# board_1_2v.net
KiCad netlist of a schematic drawn in EAGLE
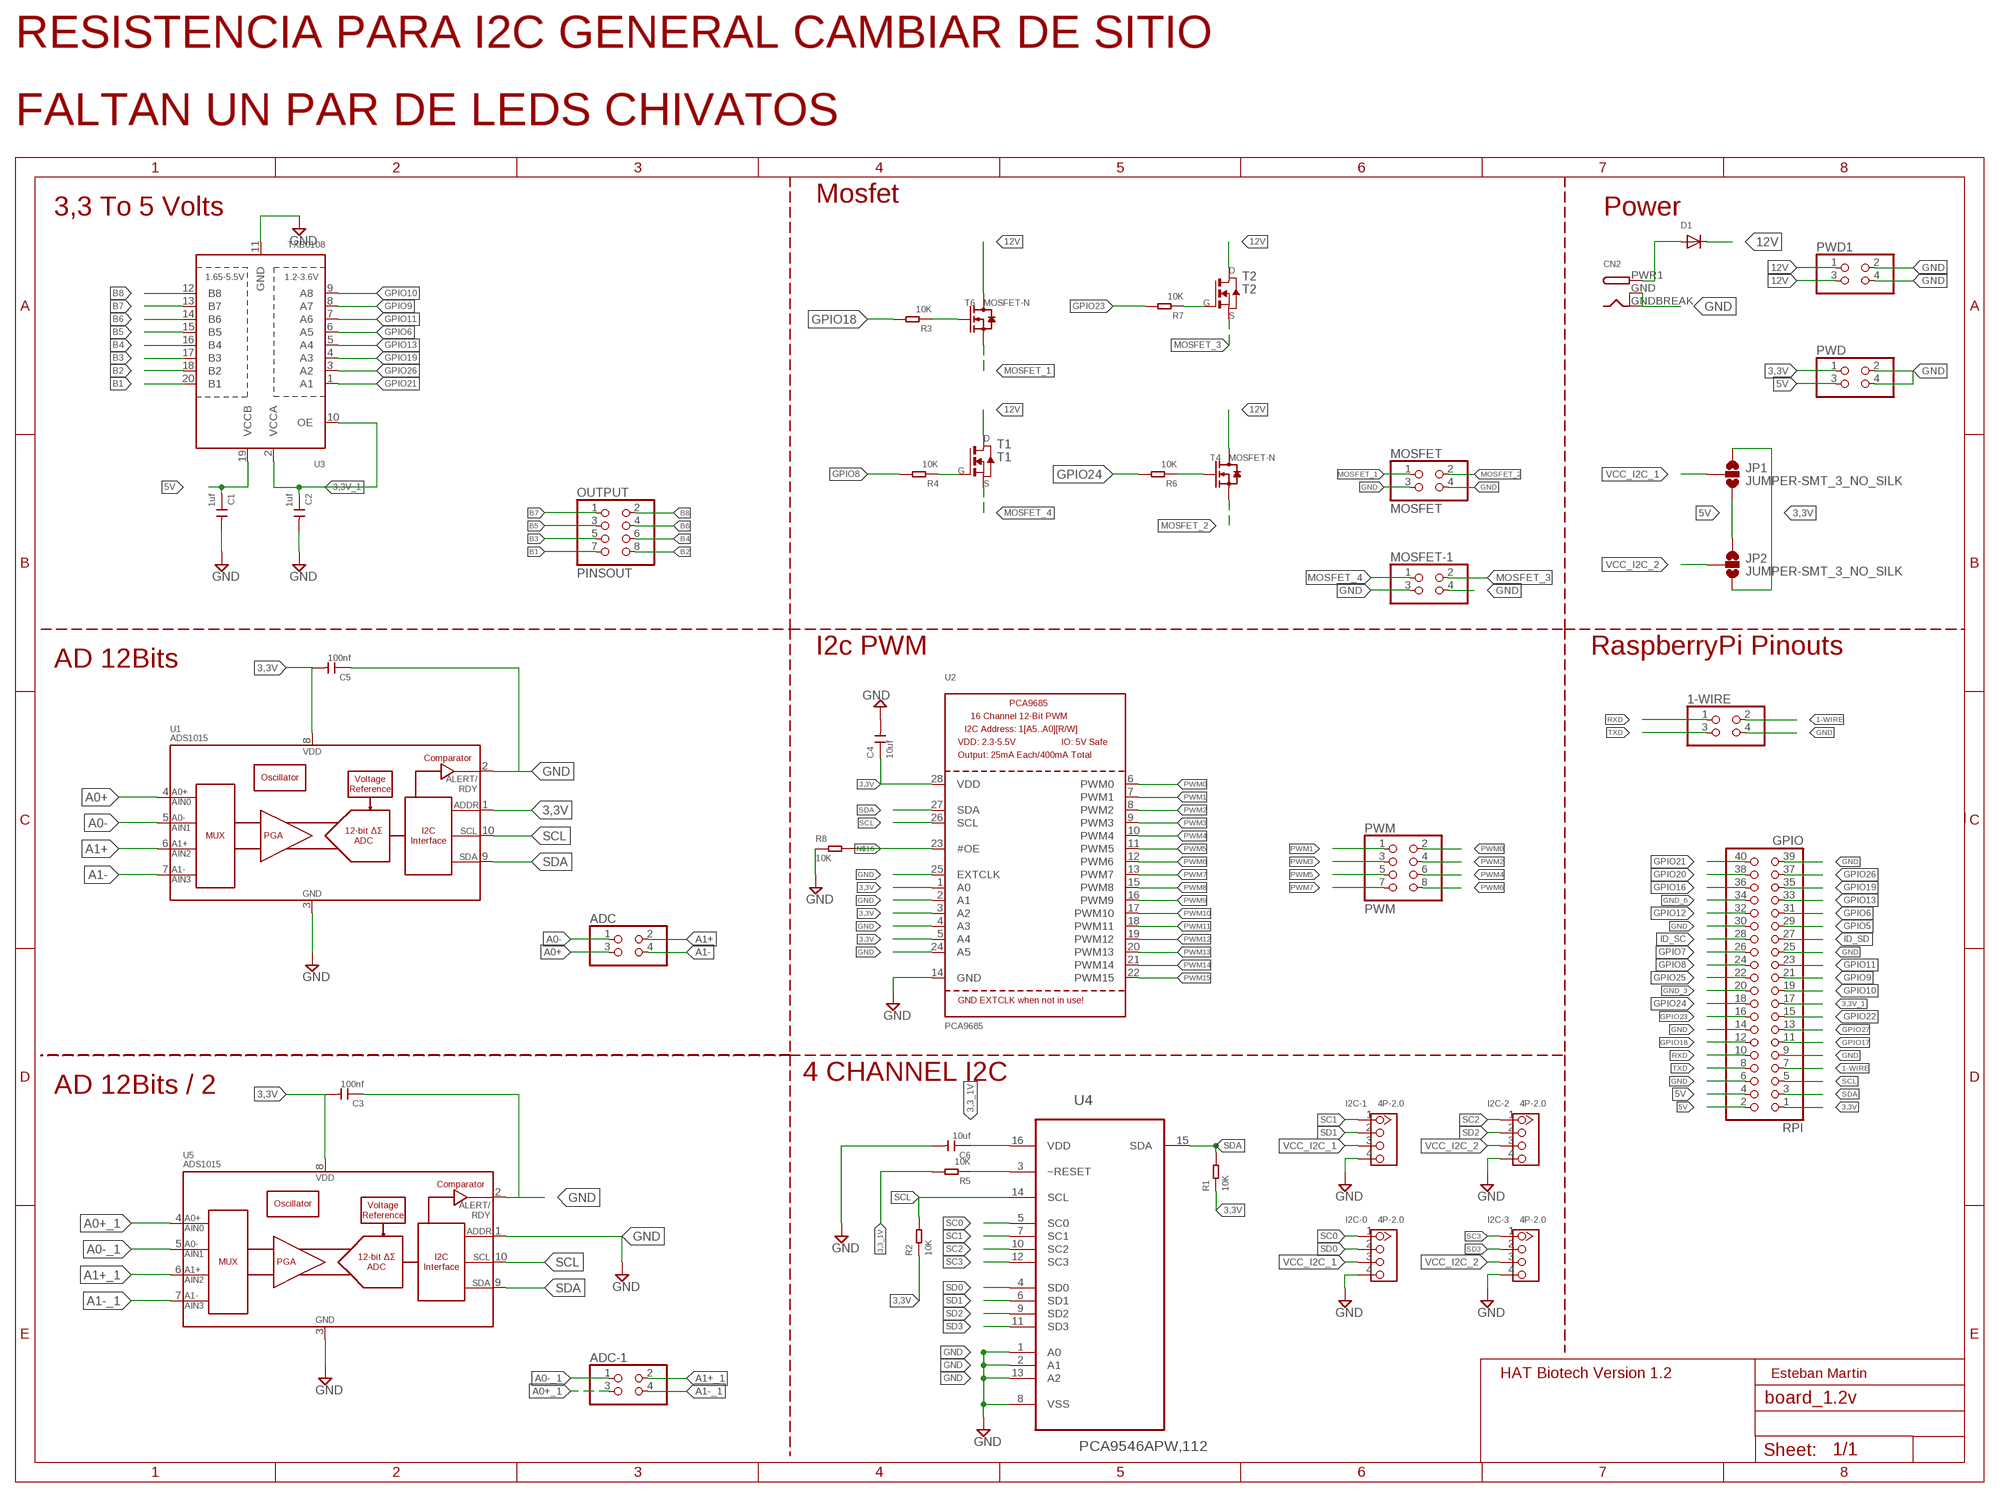
[diagram p0: schematic, sheet 1]

(export (version "E")
  (design (tool "Eeschema 10.0.6"))
  (components
    (comp (ref "1-WIRE")
      (value "PINHD-2X2")
      (footprint "eagle-import:2X02")
      (libsource (lib "eagle-import") (part "PINHD-2X2"))
    )
    (comp (ref "ADC")
      (value "PINHD-2X2")
      (footprint "eagle-import:2X02")
      (libsource (lib "eagle-import") (part "PINHD-2X2"))
    )
    (comp (ref "ADC-1")
      (value "PINHD-2X2")
      (footprint "eagle-import:2X02")
      (libsource (lib "eagle-import") (part "PINHD-2X2"))
    )
    (comp (ref "C1")
      (value "1uf")
      (footprint "eagle-import:C0805")
      (fields (field (name "MPN") "CC0805KKX7R8BB105"))
      (libsource (lib "eagle-import") (part "CERAMIC-1UF-25V-10%-X7R(0805)"))
    )
    (comp (ref "C2")
      (value "1uf")
      (footprint "eagle-import:C0805")
      (fields (field (name "MPN") "CC0805KKX7R8BB105"))
      (libsource (lib "eagle-import") (part "CERAMIC-1UF-25V-10%-X7R(0805)"))
    )
    (comp (ref "C3")
      (value "100nf")
      (footprint "eagle-import:C0805")
      (fields (field (name "MPN") "CC0805KRX7R9BB104"))
      (libsource (lib "eagle-import") (part "CERAMIC-100NF-50V-10%-X7R(0805)"))
    )
    (comp (ref "C4")
      (value "10uf")
      (footprint "eagle-import:C0805")
      (fields (field (name "MPN") "CC0805KKX7R8BB105"))
      (libsource (lib "eagle-import") (part "CERAMIC-1UF-25V-10%-X7R(0805)"))
    )
    (comp (ref "C5")
      (value "100nf")
      (footprint "eagle-import:C0805")
      (fields (field (name "MPN") "CC0805KRX7R9BB104"))
      (libsource (lib "eagle-import") (part "CERAMIC-100NF-50V-10%-X7R(0805)"))
    )
    (comp (ref "C6")
      (value "10uf")
      (footprint "eagle-import:C0805")
      (fields (field (name "MPN") "CC0805KKX7R8BB105"))
      (libsource (lib "eagle-import") (part "CERAMIC-1UF-25V-10%-X7R(0805)"))
    )
    (comp (ref "CN2")
      (value "DCBARRELSMT")
      (footprint "eagle-import:DCJACK_2MM_SMT")
      (libsource (lib "eagle-import") (part "DCBARRELSMT"))
    )
    (comp (ref "D1")
      (value "DIODESOD-123")
      (footprint "eagle-import:SOD-123")
      (libsource (lib "eagle-import") (part "DIODESOD-123"))
    )
    (comp (ref "I2C-0")
      (value "4P-2.0")
      (footprint "eagle-import:HW4-2.0")
      (libsource (lib "eagle-import") (part "GROVE-CONNECTOR-DIP(4P-2.0)"))
    )
    (comp (ref "I2C-1")
      (value "4P-2.0")
      (footprint "eagle-import:HW4-2.0")
      (libsource (lib "eagle-import") (part "GROVE-CONNECTOR-DIP(4P-2.0)"))
    )
    (comp (ref "I2C-2")
      (value "4P-2.0")
      (footprint "eagle-import:HW4-2.0")
      (libsource (lib "eagle-import") (part "GROVE-CONNECTOR-DIP(4P-2.0)"))
    )
    (comp (ref "I2C-3")
      (value "4P-2.0")
      (footprint "eagle-import:HW4-2.0")
      (libsource (lib "eagle-import") (part "GROVE-CONNECTOR-DIP(4P-2.0)"))
    )
    (comp (ref "JP1")
      (value "JUMPER-SMT_3_NO_SILK")
      (footprint "eagle-import:SMT-JUMPER_3_NO_SILK")
      (libsource (lib "eagle-import") (part "JUMPER-SMT_3_NO_SILK"))
    )
    (comp (ref "JP2")
      (value "JUMPER-SMT_3_NO_SILK")
      (footprint "eagle-import:SMT-JUMPER_3_NO_SILK")
      (libsource (lib "eagle-import") (part "JUMPER-SMT_3_NO_SILK"))
    )
    (comp (ref "MOSFET")
      (value "MOSFET")
      (footprint "eagle-import:2X02")
      (libsource (lib "eagle-import") (part "PINHD-2X2"))
    )
    (comp (ref "MOSFET-1")
      (value "PINHD-2X2")
      (footprint "eagle-import:2X02")
      (libsource (lib "eagle-import") (part "PINHD-2X2"))
    )
    (comp (ref "OUTPUT")
      (value "PINSOUT")
      (footprint "eagle-import:2X04")
      (libsource (lib "eagle-import") (part "PINHD-2X4"))
    )
    (comp (ref "PWD")
      (value "PINHD-2X2")
      (footprint "eagle-import:2X02")
      (libsource (lib "eagle-import") (part "PINHD-2X2"))
    )
    (comp (ref "PWD1")
      (value "PINHD-2X2")
      (footprint "eagle-import:2X02")
      (libsource (lib "eagle-import") (part "PINHD-2X2"))
    )
    (comp (ref "PWM")
      (value "PWM")
      (footprint "eagle-import:2X04")
      (libsource (lib "eagle-import") (part "PINHD-2X4"))
    )
    (comp (ref "R1")
      (value "10K")
      (footprint "eagle-import:R0805")
      (fields (field (name "MPN") "RC0805FR-0710KL"))
      (libsource (lib "eagle-import") (part "SMD-RES-10K-1%-1/8W(0805)"))
    )
    (comp (ref "R2")
      (value "10K")
      (footprint "eagle-import:R0805")
      (fields (field (name "MPN") "RC0805FR-0710KL"))
      (libsource (lib "eagle-import") (part "SMD-RES-10K-1%-1/8W(0805)"))
    )
    (comp (ref "R3")
      (value "10K")
      (footprint "eagle-import:R0805")
      (fields (field (name "MPN") "RC0805FR-0710KL"))
      (libsource (lib "eagle-import") (part "SMD-RES-10K-1%-1/8W(0805)"))
    )
    (comp (ref "R4")
      (value "10K")
      (footprint "eagle-import:R0805")
      (fields (field (name "MPN") "RC0805FR-0710KL"))
      (libsource (lib "eagle-import") (part "SMD-RES-10K-1%-1/8W(0805)"))
    )
    (comp (ref "R5")
      (value "10K")
      (footprint "eagle-import:R0805")
      (fields (field (name "MPN") "RC0805FR-0710KL"))
      (libsource (lib "eagle-import") (part "SMD-RES-10K-1%-1/8W(0805)"))
    )
    (comp (ref "R6")
      (value "10K")
      (footprint "eagle-import:R0805")
      (fields (field (name "MPN") "RC0805FR-0710KL"))
      (libsource (lib "eagle-import") (part "SMD-RES-10K-1%-1/8W(0805)"))
    )
    (comp (ref "R7")
      (value "10K")
      (footprint "eagle-import:R0805")
      (fields (field (name "MPN") "RC0805FR-0710KL"))
      (libsource (lib "eagle-import") (part "SMD-RES-10K-1%-1/8W(0805)"))
    )
    (comp (ref "R8")
      (value "10K")
      (footprint "eagle-import:R0805")
      (fields (field (name "MPN") "RC0805FR-0710KL"))
      (libsource (lib "eagle-import") (part "SMD-RES-10K-1%-1/8W(0805)"))
    )
    (comp (ref "RPI")
      (value "GPIO")
      (footprint "eagle-import:2X20")
      (libsource (lib "eagle-import") (part "PINHD-2X20"))
    )
    (comp (ref "T1")
      (value "T1")
      (footprint "eagle-import:TO252")
      (libsource (lib "eagle-import") (part "NMOSFETTO252"))
    )
    (comp (ref "T2")
      (value "T2")
      (footprint "eagle-import:TO252")
      (libsource (lib "eagle-import") (part "NMOSFETTO252"))
    )
    (comp (ref "T4")
      (value "MOSFET-N")
      (footprint "eagle-import:SOT-23")
      (libsource (lib "eagle-import") (part "MOSFET-N"))
    )
    (comp (ref "T6")
      (value "MOSFET-N")
      (footprint "eagle-import:SOT-23")
      (libsource (lib "eagle-import") (part "MOSFET-N"))
    )
    (comp (ref "U1")
      (value "ADS1015")
      (footprint "eagle-import:MSOP10")
      (libsource (lib "eagle-import") (part "ADS1015"))
    )
    (comp (ref "U2")
      (value "PCA9685")
      (footprint "eagle-import:TSSOP28")
      (libsource (lib "eagle-import") (part "PCA9685"))
    )
    (comp (ref "U3")
      (value "TXB0108")
      (footprint "eagle-import:TSSOP20")
      (libsource (lib "eagle-import") (part "TXB0108PWR"))
    )
    (comp (ref "U4")
      (value "PCA9546APW,112")
      (footprint "eagle-import:SOP65P640X110-16N")
      (libsource (lib "eagle-import") (part "PCA9546APW,112"))
    )
    (comp (ref "U5")
      (value "ADS1015")
      (footprint "eagle-import:MSOP10")
      (libsource (lib "eagle-import") (part "ADS1015"))
    )
  )
  (nets
    (net (code "1") (name "1-WIRE") (class "Default")
      (node (ref "1-WIRE") (pin "2") (pinfunction "2_2") (pintype "passive"))
      (node (ref "RPI") (pin "7") (pinfunction "7_7") (pintype "passive"))
    )
    (net (code "2") (name "3,3V") (class "Default")
      (node (ref "C3") (pin "2") (pinfunction "2_2") (pintype "passive"))
      (node (ref "C4") (pin "1") (pinfunction "1_1") (pintype "passive"))
      (node (ref "C5") (pin "2") (pinfunction "2_2") (pintype "passive"))
      (node (ref "JP1") (pin "1") (pinfunction "1_1") (pintype "passive"))
      (node (ref "JP2") (pin "3") (pinfunction "3_3") (pintype "passive"))
      (node (ref "PWD") (pin "1") (pinfunction "1_1") (pintype "passive"))
      (node (ref "R1") (pin "1") (pinfunction "1_1") (pintype "passive"))
      (node (ref "R2") (pin "1") (pinfunction "1_1") (pintype "passive"))
      (node (ref "RPI") (pin "1") (pinfunction "1_1") (pintype "passive"))
      (node (ref "U1") (pin "1") (pinfunction "ADDR_1") (pintype "bidirectional"))
      (node (ref "U1") (pin "8") (pinfunction "VDD_8") (pintype "bidirectional"))
      (node (ref "U2") (pin "1") (pinfunction "A0_1") (pintype "bidirectional"))
      (node (ref "U2") (pin "28") (pinfunction "VDD_28") (pintype "power_in"))
      (node (ref "U2") (pin "3") (pinfunction "A2_3") (pintype "bidirectional"))
      (node (ref "U2") (pin "5") (pinfunction "A4_5") (pintype "bidirectional"))
      (node (ref "U5") (pin "8") (pinfunction "VDD_8") (pintype "bidirectional"))
    )
    (net (code "3") (name "3,3V_1") (class "Default")
      (node (ref "C2") (pin "1") (pinfunction "1_1") (pintype "passive"))
      (node (ref "RPI") (pin "17") (pinfunction "17_17") (pintype "passive"))
      (node (ref "U3") (pin "10") (pinfunction "OE_10") (pintype "bidirectional"))
      (node (ref "U3") (pin "2") (pinfunction "VCCA_2") (pintype "bidirectional"))
    )
    (net (code "4") (name "3,3_1V") (class "Default")
      (node (ref "C6") (pin "1") (pinfunction "1_1") (pintype "passive"))
      (node (ref "R5") (pin "2") (pinfunction "2_2") (pintype "passive"))
      (node (ref "U4") (pin "16") (pinfunction "VDD_16") (pintype "power_in"))
    )
    (net (code "5") (name "5V") (class "Default")
      (node (ref "C1") (pin "1") (pinfunction "1_1") (pintype "passive"))
      (node (ref "JP1") (pin "3") (pinfunction "3_3") (pintype "passive"))
      (node (ref "JP2") (pin "1") (pinfunction "1_1") (pintype "passive"))
      (node (ref "PWD") (pin "3") (pinfunction "3_3") (pintype "passive"))
      (node (ref "RPI") (pin "2") (pinfunction "2_2") (pintype "passive"))
      (node (ref "RPI") (pin "4") (pinfunction "4_4") (pintype "passive"))
      (node (ref "U3") (pin "19") (pinfunction "VCCB_19") (pintype "bidirectional"))
    )
    (net (code "6") (name "12V") (class "Default")
      (node (ref "D1") (pin "C") (pinfunction "C_C") (pintype "passive"))
      (node (ref "PWD1") (pin "1") (pinfunction "1_1") (pintype "passive"))
      (node (ref "PWD1") (pin "3") (pinfunction "3_3") (pintype "passive"))
      (node (ref "T1") (pin "3") (pinfunction "D_3") (pintype "passive"))
      (node (ref "T2") (pin "3") (pinfunction "D_3") (pintype "passive"))
      (node (ref "T4") (pin "3") (pinfunction "D_3") (pintype "passive"))
      (node (ref "T6") (pin "3") (pinfunction "D_3") (pintype "passive"))
    )
    (net (code "7") (name "A0+") (class "Default")
      (node (ref "ADC") (pin "3") (pinfunction "3_3") (pintype "passive"))
      (node (ref "U1") (pin "4") (pinfunction "AIN0_4") (pintype "bidirectional"))
    )
    (net (code "8") (name "A0+_1") (class "Default")
      (node (ref "ADC-1") (pin "3") (pinfunction "3_3") (pintype "passive"))
      (node (ref "U5") (pin "4") (pinfunction "AIN0_4") (pintype "bidirectional"))
    )
    (net (code "9") (name "A0-") (class "Default")
      (node (ref "ADC") (pin "1") (pinfunction "1_1") (pintype "passive"))
      (node (ref "U1") (pin "5") (pinfunction "AIN1_5") (pintype "bidirectional"))
    )
    (net (code "10") (name "A0-_1") (class "Default")
      (node (ref "ADC-1") (pin "1") (pinfunction "1_1") (pintype "passive"))
      (node (ref "U5") (pin "5") (pinfunction "AIN1_5") (pintype "bidirectional"))
    )
    (net (code "11") (name "A1+") (class "Default")
      (node (ref "ADC") (pin "2") (pinfunction "2_2") (pintype "passive"))
      (node (ref "U1") (pin "6") (pinfunction "AIN2_6") (pintype "bidirectional"))
    )
    (net (code "12") (name "A1+_1") (class "Default")
      (node (ref "ADC-1") (pin "2") (pinfunction "2_2") (pintype "passive"))
      (node (ref "U5") (pin "6") (pinfunction "AIN2_6") (pintype "bidirectional"))
    )
    (net (code "13") (name "A1-") (class "Default")
      (node (ref "ADC") (pin "4") (pinfunction "4_4") (pintype "passive"))
      (node (ref "U1") (pin "7") (pinfunction "AIN3_7") (pintype "bidirectional"))
    )
    (net (code "14") (name "A1-_1") (class "Default")
      (node (ref "ADC-1") (pin "4") (pinfunction "4_4") (pintype "passive"))
      (node (ref "U5") (pin "7") (pinfunction "AIN3_7") (pintype "bidirectional"))
    )
    (net (code "15") (name "B1") (class "Default")
      (node (ref "OUTPUT") (pin "7") (pinfunction "7_7") (pintype "passive"))
      (node (ref "U3") (pin "20") (pinfunction "B1_20") (pintype "bidirectional"))
    )
    (net (code "16") (name "B2") (class "Default")
      (node (ref "OUTPUT") (pin "8") (pinfunction "8_8") (pintype "passive"))
      (node (ref "U3") (pin "18") (pinfunction "B2_18") (pintype "bidirectional"))
    )
    (net (code "17") (name "B3") (class "Default")
      (node (ref "OUTPUT") (pin "5") (pinfunction "5_5") (pintype "passive"))
      (node (ref "U3") (pin "17") (pinfunction "B3_17") (pintype "bidirectional"))
    )
    (net (code "18") (name "B4") (class "Default")
      (node (ref "OUTPUT") (pin "6") (pinfunction "6_6") (pintype "passive"))
      (node (ref "U3") (pin "16") (pinfunction "B4_16") (pintype "bidirectional"))
    )
    (net (code "19") (name "B5") (class "Default")
      (node (ref "OUTPUT") (pin "3") (pinfunction "3_3") (pintype "passive"))
      (node (ref "U3") (pin "15") (pinfunction "B5_15") (pintype "bidirectional"))
    )
    (net (code "20") (name "B6") (class "Default")
      (node (ref "OUTPUT") (pin "4") (pinfunction "4_4") (pintype "passive"))
      (node (ref "U3") (pin "14") (pinfunction "B6_14") (pintype "bidirectional"))
    )
    (net (code "21") (name "B7") (class "Default")
      (node (ref "OUTPUT") (pin "1") (pinfunction "1_1") (pintype "passive"))
      (node (ref "U3") (pin "13") (pinfunction "B7_13") (pintype "bidirectional"))
    )
    (net (code "22") (name "B8") (class "Default")
      (node (ref "OUTPUT") (pin "2") (pinfunction "2_2") (pintype "passive"))
      (node (ref "U3") (pin "12") (pinfunction "B8_12") (pintype "bidirectional"))
    )
    (net (code "23") (name "GND") (class "Default")
      (node (ref "1-WIRE") (pin "4") (pinfunction "4_4") (pintype "passive"))
      (node (ref "C1") (pin "2") (pinfunction "2_2") (pintype "passive"))
      (node (ref "C2") (pin "2") (pinfunction "2_2") (pintype "passive"))
      (node (ref "C3") (pin "1") (pinfunction "1_1") (pintype "passive"))
      (node (ref "C4") (pin "2") (pinfunction "2_2") (pintype "passive"))
      (node (ref "C5") (pin "1") (pinfunction "1_1") (pintype "passive"))
      (node (ref "C6") (pin "2") (pinfunction "2_2") (pintype "passive"))
      (node (ref "CN2") (pin "GND") (pinfunction "GNDBREAK_GND") (pintype "power_in"))
      (node (ref "CN2") (pin "GNDBREAK") (pinfunction "GND_GNDBREAK") (pintype "power_in"))
      (node (ref "I2C-0") (pin "4") (pinfunction "4_4") (pintype "bidirectional"))
      (node (ref "I2C-1") (pin "4") (pinfunction "4_4") (pintype "bidirectional"))
      (node (ref "I2C-2") (pin "4") (pinfunction "4_4") (pintype "bidirectional"))
      (node (ref "I2C-3") (pin "4") (pinfunction "4_4") (pintype "bidirectional"))
      (node (ref "MOSFET") (pin "3") (pinfunction "3_3") (pintype "passive"))
      (node (ref "MOSFET") (pin "4") (pinfunction "4_4") (pintype "passive"))
      (node (ref "MOSFET-1") (pin "3") (pinfunction "3_3") (pintype "passive"))
      (node (ref "MOSFET-1") (pin "4") (pinfunction "4_4") (pintype "passive"))
      (node (ref "PWD") (pin "2") (pinfunction "2_2") (pintype "passive"))
      (node (ref "PWD") (pin "4") (pinfunction "4_4") (pintype "passive"))
      (node (ref "PWD1") (pin "2") (pinfunction "2_2") (pintype "passive"))
      (node (ref "PWD1") (pin "4") (pinfunction "4_4") (pintype "passive"))
      (node (ref "R8") (pin "1") (pinfunction "1_1") (pintype "passive"))
      (node (ref "RPI") (pin "14") (pinfunction "14_14") (pintype "passive"))
      (node (ref "RPI") (pin "25") (pinfunction "25_25") (pintype "passive"))
      (node (ref "RPI") (pin "30") (pinfunction "30_30") (pintype "passive"))
      (node (ref "RPI") (pin "39") (pinfunction "39_39") (pintype "passive"))
      (node (ref "RPI") (pin "6") (pinfunction "6_6") (pintype "passive"))
      (node (ref "RPI") (pin "9") (pinfunction "9_9") (pintype "passive"))
      (node (ref "U1") (pin "2") (pinfunction "ALERT/RDY_2") (pintype "bidirectional"))
      (node (ref "U1") (pin "3") (pinfunction "VSS_3") (pintype "bidirectional"))
      (node (ref "U2") (pin "14") (pinfunction "GND_14") (pintype "power_in"))
      (node (ref "U2") (pin "2") (pinfunction "A1_2") (pintype "bidirectional"))
      (node (ref "U2") (pin "24") (pinfunction "A5_24") (pintype "bidirectional"))
      (node (ref "U2") (pin "25") (pinfunction "EXTCLK_25") (pintype "input"))
      (node (ref "U2") (pin "4") (pinfunction "A3_4") (pintype "bidirectional"))
      (node (ref "U3") (pin "11") (pinfunction "GND_11") (pintype "bidirectional"))
      (node (ref "U4") (pin "1") (pinfunction "A0_1") (pintype "input"))
      (node (ref "U4") (pin "13") (pinfunction "A2_13") (pintype "input"))
      (node (ref "U4") (pin "2") (pinfunction "A1_2") (pintype "input"))
      (node (ref "U4") (pin "8") (pinfunction "VSS_8") (pintype "passive"))
      (node (ref "U5") (pin "1") (pinfunction "ADDR_1") (pintype "bidirectional"))
      (node (ref "U5") (pin "2") (pinfunction "ALERT/RDY_2") (pintype "bidirectional"))
      (node (ref "U5") (pin "3") (pinfunction "VSS_3") (pintype "bidirectional"))
    )
    (net (code "24") (name "GND_3") (class "Default")
      (node (ref "RPI") (pin "20") (pinfunction "20_20") (pintype "passive"))
    )
    (net (code "25") (name "GND_6") (class "Default")
      (node (ref "RPI") (pin "34") (pinfunction "34_34") (pintype "passive"))
    )
    (net (code "26") (name "GPIO5") (class "Default")
      (node (ref "RPI") (pin "29") (pinfunction "29_29") (pintype "passive"))
    )
    (net (code "27") (name "GPIO6") (class "Default")
      (node (ref "RPI") (pin "31") (pinfunction "31_31") (pintype "passive"))
      (node (ref "U3") (pin "6") (pinfunction "A5_6") (pintype "bidirectional"))
    )
    (net (code "28") (name "GPIO7") (class "Default")
      (node (ref "RPI") (pin "26") (pinfunction "26_26") (pintype "passive"))
    )
    (net (code "29") (name "GPIO8") (class "Default")
      (node (ref "R4") (pin "2") (pinfunction "2_2") (pintype "passive"))
      (node (ref "RPI") (pin "24") (pinfunction "24_24") (pintype "passive"))
    )
    (net (code "30") (name "GPIO9") (class "Default")
      (node (ref "RPI") (pin "21") (pinfunction "21_21") (pintype "passive"))
      (node (ref "U3") (pin "8") (pinfunction "A7_8") (pintype "bidirectional"))
    )
    (net (code "31") (name "GPIO10") (class "Default")
      (node (ref "RPI") (pin "19") (pinfunction "19_19") (pintype "passive"))
      (node (ref "U3") (pin "9") (pinfunction "A8_9") (pintype "bidirectional"))
    )
    (net (code "32") (name "GPIO11") (class "Default")
      (node (ref "RPI") (pin "23") (pinfunction "23_23") (pintype "passive"))
      (node (ref "U3") (pin "7") (pinfunction "A6_7") (pintype "bidirectional"))
    )
    (net (code "33") (name "GPIO12") (class "Default")
      (node (ref "RPI") (pin "32") (pinfunction "32_32") (pintype "passive"))
    )
    (net (code "34") (name "GPIO13") (class "Default")
      (node (ref "RPI") (pin "33") (pinfunction "33_33") (pintype "passive"))
      (node (ref "U3") (pin "5") (pinfunction "A4_5") (pintype "bidirectional"))
    )
    (net (code "35") (name "GPIO16") (class "Default")
      (node (ref "RPI") (pin "36") (pinfunction "36_36") (pintype "passive"))
    )
    (net (code "36") (name "GPIO17") (class "Default")
      (node (ref "RPI") (pin "11") (pinfunction "11_11") (pintype "passive"))
    )
    (net (code "37") (name "GPIO18") (class "Default")
      (node (ref "R3") (pin "2") (pinfunction "2_2") (pintype "passive"))
      (node (ref "RPI") (pin "12") (pinfunction "12_12") (pintype "passive"))
    )
    (net (code "38") (name "GPIO19") (class "Default")
      (node (ref "RPI") (pin "35") (pinfunction "35_35") (pintype "passive"))
      (node (ref "U3") (pin "4") (pinfunction "A3_4") (pintype "bidirectional"))
    )
    (net (code "39") (name "GPIO20") (class "Default")
      (node (ref "RPI") (pin "38") (pinfunction "38_38") (pintype "passive"))
    )
    (net (code "40") (name "GPIO21") (class "Default")
      (node (ref "RPI") (pin "40") (pinfunction "40_40") (pintype "passive"))
      (node (ref "U3") (pin "1") (pinfunction "A1_1") (pintype "bidirectional"))
    )
    (net (code "41") (name "GPIO22") (class "Default")
      (node (ref "RPI") (pin "15") (pinfunction "15_15") (pintype "passive"))
    )
    (net (code "42") (name "GPIO23") (class "Default")
      (node (ref "R7") (pin "2") (pinfunction "2_2") (pintype "passive"))
      (node (ref "RPI") (pin "16") (pinfunction "16_16") (pintype "passive"))
    )
    (net (code "43") (name "GPIO24") (class "Default")
      (node (ref "R6") (pin "2") (pinfunction "2_2") (pintype "passive"))
      (node (ref "RPI") (pin "18") (pinfunction "18_18") (pintype "passive"))
    )
    (net (code "44") (name "GPIO25") (class "Default")
      (node (ref "RPI") (pin "22") (pinfunction "22_22") (pintype "passive"))
    )
    (net (code "45") (name "GPIO26") (class "Default")
      (node (ref "RPI") (pin "37") (pinfunction "37_37") (pintype "passive"))
      (node (ref "U3") (pin "3") (pinfunction "A2_3") (pintype "bidirectional"))
    )
    (net (code "46") (name "GPIO27") (class "Default")
      (node (ref "RPI") (pin "13") (pinfunction "13_13") (pintype "passive"))
    )
    (net (code "47") (name "ID_SC") (class "Default")
      (node (ref "RPI") (pin "28") (pinfunction "28_28") (pintype "passive"))
    )
    (net (code "48") (name "ID_SD") (class "Default")
      (node (ref "RPI") (pin "27") (pinfunction "27_27") (pintype "passive"))
    )
    (net (code "49") (name "MOSFET_1") (class "Default")
      (node (ref "MOSFET") (pin "1") (pinfunction "1_1") (pintype "passive"))
      (node (ref "T6") (pin "2") (pinfunction "S_2") (pintype "passive"))
    )
    (net (code "50") (name "MOSFET_2") (class "Default")
      (node (ref "MOSFET") (pin "2") (pinfunction "2_2") (pintype "passive"))
      (node (ref "T4") (pin "2") (pinfunction "S_2") (pintype "passive"))
    )
    (net (code "51") (name "MOSFET_3") (class "Default")
      (node (ref "MOSFET-1") (pin "2") (pinfunction "2_2") (pintype "passive"))
      (node (ref "T2") (pin "2") (pinfunction "S_2") (pintype "passive"))
    )
    (net (code "52") (name "MOSFET_4") (class "Default")
      (node (ref "MOSFET-1") (pin "1") (pinfunction "1_1") (pintype "passive"))
      (node (ref "T1") (pin "2") (pinfunction "S_2") (pintype "passive"))
    )
    (net (code "53") (name "N$16") (class "Default")
      (node (ref "R8") (pin "2") (pinfunction "2_2") (pintype "passive"))
      (node (ref "U2") (pin "23") (pinfunction "#OE_23") (pintype "input"))
    )
    (net (code "54") (name "Net-(CN2-PWR)") (class "Default")
      (node (ref "CN2") (pin "PWR1") (pinfunction "PWR_PWR1") (pintype "power_in"))
      (node (ref "D1") (pin "A") (pinfunction "A_A") (pintype "passive"))
    )
    (net (code "55") (name "Net-(T1-G)") (class "Default")
      (node (ref "R4") (pin "1") (pinfunction "1_1") (pintype "passive"))
      (node (ref "T1") (pin "1") (pinfunction "G_1") (pintype "passive"))
    )
    (net (code "56") (name "Net-(T2-G)") (class "Default")
      (node (ref "R7") (pin "1") (pinfunction "1_1") (pintype "passive"))
      (node (ref "T2") (pin "1") (pinfunction "G_1") (pintype "passive"))
    )
    (net (code "57") (name "Net-(T4-G)") (class "Default")
      (node (ref "R6") (pin "1") (pinfunction "1_1") (pintype "passive"))
      (node (ref "T4") (pin "1") (pinfunction "G_1") (pintype "passive"))
    )
    (net (code "58") (name "Net-(T6-G)") (class "Default")
      (node (ref "R3") (pin "1") (pinfunction "1_1") (pintype "passive"))
      (node (ref "T6") (pin "1") (pinfunction "G_1") (pintype "passive"))
    )
    (net (code "59") (name "Net-(U4-~{RESET})") (class "Default")
      (node (ref "R5") (pin "1") (pinfunction "1_1") (pintype "passive"))
      (node (ref "U4") (pin "3") (pinfunction "~{RESET}_3") (pintype "input"))
    )
    (net (code "60") (name "PWM0") (class "Default")
      (node (ref "PWM") (pin "2") (pinfunction "2_2") (pintype "passive"))
      (node (ref "U2") (pin "6") (pinfunction "PWM0_6") (pintype "output"))
    )
    (net (code "61") (name "PWM1") (class "Default")
      (node (ref "PWM") (pin "1") (pinfunction "1_1") (pintype "passive"))
      (node (ref "U2") (pin "7") (pinfunction "PWM1_7") (pintype "output"))
    )
    (net (code "62") (name "PWM2") (class "Default")
      (node (ref "PWM") (pin "4") (pinfunction "4_4") (pintype "passive"))
      (node (ref "U2") (pin "8") (pinfunction "PWM2_8") (pintype "output"))
    )
    (net (code "63") (name "PWM3") (class "Default")
      (node (ref "PWM") (pin "3") (pinfunction "3_3") (pintype "passive"))
      (node (ref "U2") (pin "9") (pinfunction "PWM3_9") (pintype "output"))
    )
    (net (code "64") (name "PWM4") (class "Default")
      (node (ref "PWM") (pin "6") (pinfunction "6_6") (pintype "passive"))
      (node (ref "U2") (pin "10") (pinfunction "PWM4_10") (pintype "output"))
    )
    (net (code "65") (name "PWM5") (class "Default")
      (node (ref "PWM") (pin "5") (pinfunction "5_5") (pintype "passive"))
      (node (ref "U2") (pin "11") (pinfunction "PWM5_11") (pintype "output"))
    )
    (net (code "66") (name "PWM6") (class "Default")
      (node (ref "PWM") (pin "8") (pinfunction "8_8") (pintype "passive"))
      (node (ref "U2") (pin "12") (pinfunction "PWM6_12") (pintype "output"))
    )
    (net (code "67") (name "PWM7") (class "Default")
      (node (ref "PWM") (pin "7") (pinfunction "7_7") (pintype "passive"))
      (node (ref "U2") (pin "13") (pinfunction "PWM7_13") (pintype "output"))
    )
    (net (code "68") (name "PWM8") (class "Default")
      (node (ref "U2") (pin "15") (pinfunction "PWM8_15") (pintype "output"))
    )
    (net (code "69") (name "PWM9") (class "Default")
      (node (ref "U2") (pin "16") (pinfunction "PWM9_16") (pintype "output"))
    )
    (net (code "70") (name "PWM10") (class "Default")
      (node (ref "U2") (pin "17") (pinfunction "PWM10_17") (pintype "output"))
    )
    (net (code "71") (name "PWM11") (class "Default")
      (node (ref "U2") (pin "18") (pinfunction "PWM11_18") (pintype "output"))
    )
    (net (code "72") (name "PWM12") (class "Default")
      (node (ref "U2") (pin "19") (pinfunction "PWM12_19") (pintype "output"))
    )
    (net (code "73") (name "PWM13") (class "Default")
      (node (ref "U2") (pin "20") (pinfunction "PWM13_20") (pintype "output"))
    )
    (net (code "74") (name "PWM14") (class "Default")
      (node (ref "U2") (pin "21") (pinfunction "PWM14_21") (pintype "output"))
    )
    (net (code "75") (name "PWM15") (class "Default")
      (node (ref "U2") (pin "22") (pinfunction "PWM15_22") (pintype "output"))
    )
    (net (code "76") (name "RXD") (class "Default")
      (node (ref "1-WIRE") (pin "1") (pinfunction "1_1") (pintype "passive"))
      (node (ref "RPI") (pin "10") (pinfunction "10_10") (pintype "passive"))
    )
    (net (code "77") (name "SC0") (class "Default")
      (node (ref "I2C-0") (pin "1") (pinfunction "1_1") (pintype "bidirectional"))
      (node (ref "U4") (pin "5") (pinfunction "SC0_5") (pintype "input"))
    )
    (net (code "78") (name "SC1") (class "Default")
      (node (ref "I2C-1") (pin "1") (pinfunction "1_1") (pintype "bidirectional"))
      (node (ref "U4") (pin "7") (pinfunction "SC1_7") (pintype "input"))
    )
    (net (code "79") (name "SC2") (class "Default")
      (node (ref "I2C-2") (pin "1") (pinfunction "1_1") (pintype "bidirectional"))
      (node (ref "U4") (pin "10") (pinfunction "SC2_10") (pintype "input"))
    )
    (net (code "80") (name "SC3") (class "Default")
      (node (ref "I2C-3") (pin "1") (pinfunction "1_1") (pintype "bidirectional"))
      (node (ref "U4") (pin "12") (pinfunction "SC3_12") (pintype "input"))
    )
    (net (code "81") (name "SCL") (class "Default")
      (node (ref "R2") (pin "2") (pinfunction "2_2") (pintype "passive"))
      (node (ref "RPI") (pin "5") (pinfunction "5_5") (pintype "passive"))
      (node (ref "U1") (pin "10") (pinfunction "SCL_10") (pintype "bidirectional"))
      (node (ref "U2") (pin "26") (pinfunction "SCL_26") (pintype "bidirectional"))
      (node (ref "U4") (pin "14") (pinfunction "SCL_14") (pintype "bidirectional"))
      (node (ref "U5") (pin "10") (pinfunction "SCL_10") (pintype "bidirectional"))
    )
    (net (code "82") (name "SD0") (class "Default")
      (node (ref "I2C-0") (pin "2") (pinfunction "2_2") (pintype "bidirectional"))
      (node (ref "U4") (pin "4") (pinfunction "SD0_4") (pintype "input"))
    )
    (net (code "83") (name "SD1") (class "Default")
      (node (ref "I2C-1") (pin "2") (pinfunction "2_2") (pintype "bidirectional"))
      (node (ref "U4") (pin "6") (pinfunction "SD1_6") (pintype "input"))
    )
    (net (code "84") (name "SD2") (class "Default")
      (node (ref "I2C-2") (pin "2") (pinfunction "2_2") (pintype "bidirectional"))
      (node (ref "U4") (pin "9") (pinfunction "SD2_9") (pintype "input"))
    )
    (net (code "85") (name "SD3") (class "Default")
      (node (ref "I2C-3") (pin "2") (pinfunction "2_2") (pintype "bidirectional"))
      (node (ref "U4") (pin "11") (pinfunction "SD3_11") (pintype "input"))
    )
    (net (code "86") (name "SDA") (class "Default")
      (node (ref "R1") (pin "2") (pinfunction "2_2") (pintype "passive"))
      (node (ref "RPI") (pin "3") (pinfunction "3_3") (pintype "passive"))
      (node (ref "U1") (pin "9") (pinfunction "SDA_9") (pintype "bidirectional"))
      (node (ref "U2") (pin "27") (pinfunction "SDA_27") (pintype "bidirectional"))
      (node (ref "U4") (pin "15") (pinfunction "SDA_15") (pintype "bidirectional"))
      (node (ref "U5") (pin "9") (pinfunction "SDA_9") (pintype "bidirectional"))
    )
    (net (code "87") (name "TXD") (class "Default")
      (node (ref "1-WIRE") (pin "3") (pinfunction "3_3") (pintype "passive"))
      (node (ref "RPI") (pin "8") (pinfunction "8_8") (pintype "passive"))
    )
    (net (code "88") (name "VCC_I2C_1") (class "Default")
      (node (ref "I2C-0") (pin "3") (pinfunction "3_3") (pintype "bidirectional"))
      (node (ref "I2C-1") (pin "3") (pinfunction "3_3") (pintype "bidirectional"))
      (node (ref "JP1") (pin "2") (pinfunction "2_2") (pintype "passive"))
    )
    (net (code "89") (name "VCC_I2C_2") (class "Default")
      (node (ref "I2C-2") (pin "3") (pinfunction "3_3") (pintype "bidirectional"))
      (node (ref "I2C-3") (pin "3") (pinfunction "3_3") (pintype "bidirectional"))
      (node (ref "JP2") (pin "2") (pinfunction "2_2") (pintype "passive"))
    )
  )
)
